# flexpcb_segmented.net
KiCad netlist of a schematic drawn in EAGLE
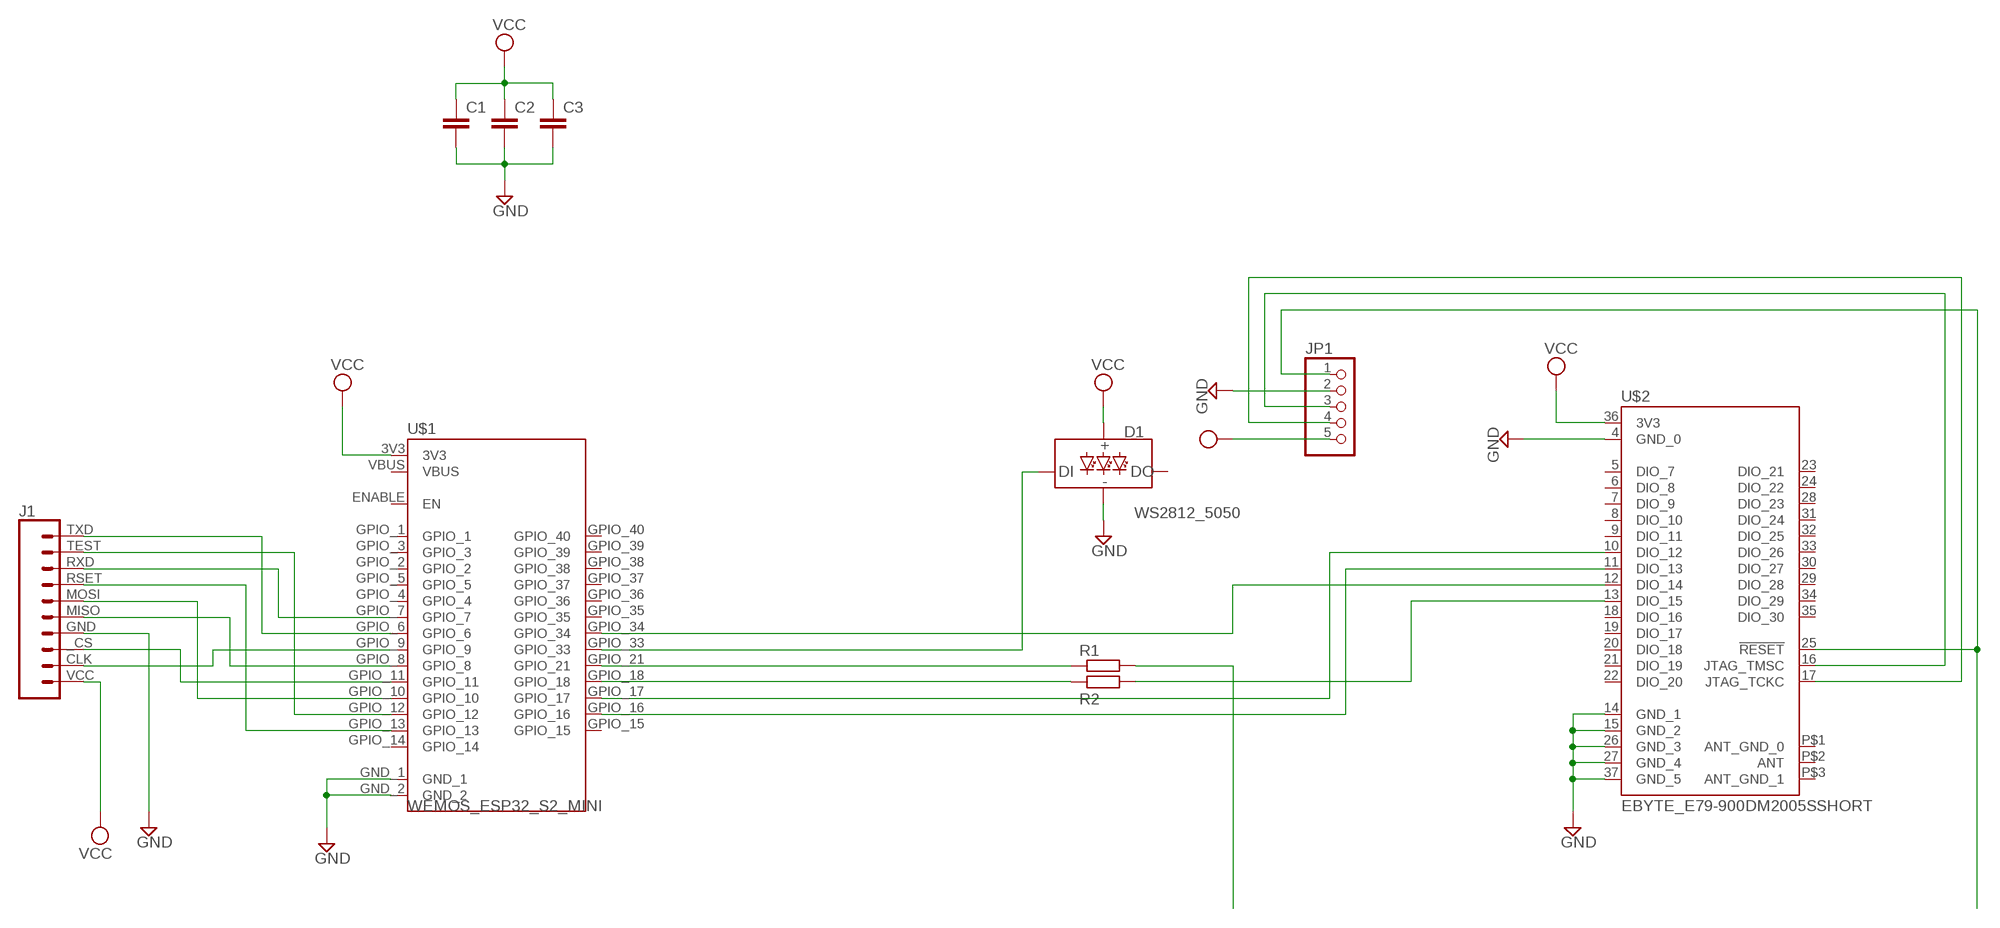
[diagram p0: schematic, sheet 1]

(export (version "E")
  (design (tool "Eeschema 10.0.6"))
  (components
    (comp (ref "C1")
      (value "C-EUC1206")
      (footprint "eagle-import:C1206")
      (libsource (lib "eagle-import") (part "C-EUC1206"))
    )
    (comp (ref "C2")
      (value "C-EUC1206")
      (footprint "eagle-import:C1206")
      (libsource (lib "eagle-import") (part "C-EUC1206"))
    )
    (comp (ref "C3")
      (value "C-EUC1206")
      (footprint "eagle-import:C1206")
      (libsource (lib "eagle-import") (part "C-EUC1206"))
    )
    (comp (ref "D1")
      (value "WS2812_5050")
      (footprint "eagle-import:WS2812-5X5-4PIN")
      (libsource (lib "eagle-import") (part "WS2812_5050"))
    )
    (comp (ref "J1")
      (value "SOLUM_ZBS_DEBUGSEGMENTED_DISPLAY")
      (footprint "eagle-import:SOLUM_ZBS_DEBUG_SEG")
      (libsource (lib "eagle-import") (part "SOLUM_ZBS_DEBUGSEGMENTED_DISPLAY"))
    )
    (comp (ref "JP1")
      (value "PINHD-1X55X2MM")
      (footprint "eagle-import:1_05X2MM")
      (libsource (lib "eagle-import") (part "PINHD-1X55X2MM"))
    )
    (comp (ref "R1")
      (value "R-EU_R0805")
      (footprint "eagle-import:R0805")
      (libsource (lib "eagle-import") (part "R-EU_R0805"))
    )
    (comp (ref "R2")
      (value "R-EU_R0805")
      (footprint "eagle-import:R0805")
      (libsource (lib "eagle-import") (part "R-EU_R0805"))
    )
    (comp (ref "U$1")
      (value "WEMOS_ESP32_S2_MINI")
      (footprint "eagle-import:WEMOS_ESP32_S2_MINI")
      (libsource (lib "eagle-import") (part "WEMOS_ESP32_S2_MINI"))
    )
    (comp (ref "U$2")
      (value "EBYTE_E79-900DM2005SSHORT")
      (footprint "eagle-import:EBYTE_E79-900DM2005S_PARTIAL")
      (libsource (lib "eagle-import") (part "EBYTE_E79-900DM2005SSHORT"))
    )
  )
  (nets
    (net (code "1") (name "/ANT") (class "Default")
      (node (ref "U$2") (pin "P$2") (pinfunction "ANT_P$2") (pintype "power_in"))
    )
    (net (code "2") (name "/ANT_GND_0") (class "Default")
      (node (ref "U$2") (pin "P$1") (pinfunction "ANT_GND_0_P$1") (pintype "power_in"))
    )
    (net (code "3") (name "/ANT_GND_1") (class "Default")
      (node (ref "U$2") (pin "P$3") (pinfunction "ANT_GND_1_P$3") (pintype "power_in"))
    )
    (net (code "4") (name "/VBUS") (class "Default")
      (node (ref "U$1") (pin "VBUS") (pinfunction "VBUS_VBUS") (pintype "power_in"))
    )
    (net (code "5") (name "GND") (class "Default")
      (node (ref "C1") (pin "2") (pinfunction "2_2") (pintype "passive"))
      (node (ref "C2") (pin "2") (pinfunction "2_2") (pintype "passive"))
      (node (ref "C3") (pin "2") (pinfunction "2_2") (pintype "passive"))
      (node (ref "D1") (pin "GND") (pinfunction "GND_GND") (pintype "bidirectional"))
      (node (ref "J1") (pin "GND") (pinfunction "4_GND") (pintype "passive"))
      (node (ref "JP1") (pin "2") (pinfunction "2_2") (pintype "passive"))
      (node (ref "U$1") (pin "GND_1") (pinfunction "GND_1_GND_1") (pintype "power_in"))
      (node (ref "U$1") (pin "GND_2") (pinfunction "GND_2_GND_2") (pintype "power_in"))
      (node (ref "U$2") (pin "14") (pinfunction "GND_1_14") (pintype "power_in"))
      (node (ref "U$2") (pin "15") (pinfunction "GND_2_15") (pintype "power_in"))
      (node (ref "U$2") (pin "26") (pinfunction "GND_3_26") (pintype "power_in"))
      (node (ref "U$2") (pin "27") (pinfunction "GND_4_27") (pintype "power_in"))
      (node (ref "U$2") (pin "37") (pinfunction "GND_5_37") (pintype "power_in"))
      (node (ref "U$2") (pin "4") (pinfunction "GND_0_4") (pintype "power_in"))
    )
    (net (code "6") (name "Net-(D1-PadDI)") (class "Default")
      (node (ref "D1") (pin "DI") (pinfunction "DI_DI") (pintype "bidirectional"))
      (node (ref "U$1") (pin "GPIO_33") (pinfunction "GPIO_33_GPIO_33") (pintype "bidirectional"))
    )
    (net (code "7") (name "Net-(J1-2)") (class "Default")
      (node (ref "J1") (pin "CLK") (pinfunction "2_CLK") (pintype "passive"))
      (node (ref "U$1") (pin "GPIO_9") (pinfunction "GPIO_9_GPIO_9") (pintype "bidirectional"))
    )
    (net (code "8") (name "Net-(J1-3)") (class "Default")
      (node (ref "J1") (pin "_CS") (pinfunction "3__CS") (pintype "passive"))
      (node (ref "U$1") (pin "GPIO_11") (pinfunction "GPIO_11_GPIO_11") (pintype "bidirectional"))
    )
    (net (code "9") (name "Net-(J1-5)") (class "Default")
      (node (ref "J1") (pin "MISO") (pinfunction "5_MISO") (pintype "passive"))
      (node (ref "U$1") (pin "GPIO_8") (pinfunction "GPIO_8_GPIO_8") (pintype "bidirectional"))
    )
    (net (code "10") (name "Net-(J1-6)") (class "Default")
      (node (ref "J1") (pin "MOSI") (pinfunction "6_MOSI") (pintype "passive"))
      (node (ref "U$1") (pin "GPIO_10") (pinfunction "GPIO_10_GPIO_10") (pintype "bidirectional"))
    )
    (net (code "11") (name "Net-(J1-7)") (class "Default")
      (node (ref "J1") (pin "RSET") (pinfunction "7_RSET") (pintype "passive"))
      (node (ref "U$1") (pin "GPIO_13") (pinfunction "GPIO_13_GPIO_13") (pintype "bidirectional"))
    )
    (net (code "12") (name "Net-(J1-8)") (class "Default")
      (node (ref "J1") (pin "RXD") (pinfunction "8_RXD") (pintype "passive"))
      (node (ref "U$1") (pin "GPIO_7") (pinfunction "GPIO_7_GPIO_7") (pintype "bidirectional"))
    )
    (net (code "13") (name "Net-(J1-9)") (class "Default")
      (node (ref "J1") (pin "TEST") (pinfunction "9_TEST") (pintype "passive"))
      (node (ref "U$1") (pin "GPIO_12") (pinfunction "GPIO_12_GPIO_12") (pintype "bidirectional"))
    )
    (net (code "14") (name "Net-(J1-10)") (class "Default")
      (node (ref "J1") (pin "TXD") (pinfunction "10_TXD") (pintype "passive"))
      (node (ref "U$1") (pin "GPIO_6") (pinfunction "GPIO_6_GPIO_6") (pintype "bidirectional"))
    )
    (net (code "15") (name "Net-(R1-Pad1)") (class "Default")
      (node (ref "R1") (pin "1") (pinfunction "1_1") (pintype "passive"))
      (node (ref "U$1") (pin "GPIO_21") (pinfunction "GPIO_21_GPIO_21") (pintype "bidirectional"))
    )
    (net (code "16") (name "Net-(R2-Pad1)") (class "Default")
      (node (ref "R2") (pin "1") (pinfunction "1_1") (pintype "passive"))
      (node (ref "U$1") (pin "GPIO_18") (pinfunction "GPIO_18_GPIO_18") (pintype "bidirectional"))
    )
    (net (code "17") (name "Net-(U$2-DIO_12)") (class "Default")
      (node (ref "U$1") (pin "GPIO_17") (pinfunction "GPIO_17_GPIO_17") (pintype "bidirectional"))
      (node (ref "U$2") (pin "10") (pinfunction "DIO_12_10") (pintype "bidirectional"))
    )
    (net (code "18") (name "Net-(U$2-DIO_13)") (class "Default")
      (node (ref "U$1") (pin "GPIO_16") (pinfunction "GPIO_16_GPIO_16") (pintype "bidirectional"))
      (node (ref "U$2") (pin "11") (pinfunction "DIO_13_11") (pintype "bidirectional"))
    )
    (net (code "19") (name "Net-(U$2-DIO_14)") (class "Default")
      (node (ref "U$1") (pin "GPIO_34") (pinfunction "GPIO_34_GPIO_34") (pintype "bidirectional"))
      (node (ref "U$2") (pin "12") (pinfunction "DIO_14_12") (pintype "bidirectional"))
    )
    (net (code "20") (name "Net-(U$2-DIO_15)") (class "Default")
      (node (ref "R2") (pin "2") (pinfunction "2_2") (pintype "passive"))
      (node (ref "U$2") (pin "13") (pinfunction "DIO_15_13") (pintype "bidirectional"))
    )
    (net (code "21") (name "Net-(U$2-JTAG_TCKC)") (class "Default")
      (node (ref "JP1") (pin "4") (pinfunction "4_4") (pintype "passive"))
      (node (ref "U$2") (pin "17") (pinfunction "JTAG_TCKC_17") (pintype "bidirectional"))
    )
    (net (code "22") (name "Net-(U$2-JTAG_TMSC)") (class "Default")
      (node (ref "JP1") (pin "3") (pinfunction "3_3") (pintype "passive"))
      (node (ref "U$2") (pin "16") (pinfunction "JTAG_TMSC_16") (pintype "bidirectional"))
    )
    (net (code "23") (name "Net-(U$2-~{RESET})") (class "Default")
      (node (ref "JP1") (pin "1") (pinfunction "1_1") (pintype "passive"))
      (node (ref "U$2") (pin "25") (pinfunction "~{RESET}_25") (pintype "bidirectional"))
    )
    (net (code "24") (name "VCC") (class "Default")
      (node (ref "C1") (pin "1") (pinfunction "1_1") (pintype "passive"))
      (node (ref "C2") (pin "1") (pinfunction "1_1") (pintype "passive"))
      (node (ref "C3") (pin "1") (pinfunction "1_1") (pintype "passive"))
      (node (ref "D1") (pin "VCC") (pinfunction "VCC_VCC") (pintype "bidirectional"))
      (node (ref "J1") (pin "VCC") (pinfunction "1_VCC") (pintype "passive"))
      (node (ref "JP1") (pin "5") (pinfunction "5_5") (pintype "passive"))
      (node (ref "U$1") (pin "3V3") (pinfunction "3V3_3V3") (pintype "power_in"))
      (node (ref "U$2") (pin "36") (pinfunction "3V3_36") (pintype "power_in"))
    )
    (net (code "25") (name "unconnected-(D1-PadDO)") (class "Default")
      (node (ref "D1") (pin "DO") (pinfunction "DO_DO") (pintype "bidirectional"))
    )
    (net (code "26") (name "unconnected-(R1-Pad2)") (class "Default")
      (node (ref "R1") (pin "2") (pinfunction "2_2") (pintype "passive"))
    )
    (net (code "27") (name "unconnected-(U$1-EN-PadENABLE)") (class "Default")
      (node (ref "U$1") (pin "ENABLE") (pinfunction "EN_ENABLE") (pintype "bidirectional"))
    )
    (net (code "28") (name "unconnected-(U$1-PadGPIO_1)") (class "Default")
      (node (ref "U$1") (pin "GPIO_1") (pinfunction "GPIO_1_GPIO_1") (pintype "bidirectional"))
    )
    (net (code "29") (name "unconnected-(U$1-PadGPIO_2)") (class "Default")
      (node (ref "U$1") (pin "GPIO_2") (pinfunction "GPIO_2_GPIO_2") (pintype "bidirectional"))
    )
    (net (code "30") (name "unconnected-(U$1-PadGPIO_3)") (class "Default")
      (node (ref "U$1") (pin "GPIO_3") (pinfunction "GPIO_3_GPIO_3") (pintype "bidirectional"))
    )
    (net (code "31") (name "unconnected-(U$1-PadGPIO_4)") (class "Default")
      (node (ref "U$1") (pin "GPIO_4") (pinfunction "GPIO_4_GPIO_4") (pintype "bidirectional"))
    )
    (net (code "32") (name "unconnected-(U$1-PadGPIO_5)") (class "Default")
      (node (ref "U$1") (pin "GPIO_5") (pinfunction "GPIO_5_GPIO_5") (pintype "bidirectional"))
    )
    (net (code "33") (name "unconnected-(U$1-PadGPIO_14)") (class "Default")
      (node (ref "U$1") (pin "GPIO_14") (pinfunction "GPIO_14_GPIO_14") (pintype "bidirectional"))
    )
    (net (code "34") (name "unconnected-(U$1-PadGPIO_15)") (class "Default")
      (node (ref "U$1") (pin "GPIO_15") (pinfunction "GPIO_15_GPIO_15") (pintype "bidirectional"))
    )
    (net (code "35") (name "unconnected-(U$1-PadGPIO_35)") (class "Default")
      (node (ref "U$1") (pin "GPIO_35") (pinfunction "GPIO_35_GPIO_35") (pintype "bidirectional"))
    )
    (net (code "36") (name "unconnected-(U$1-PadGPIO_36)") (class "Default")
      (node (ref "U$1") (pin "GPIO_36") (pinfunction "GPIO_36_GPIO_36") (pintype "bidirectional"))
    )
    (net (code "37") (name "unconnected-(U$1-PadGPIO_37)") (class "Default")
      (node (ref "U$1") (pin "GPIO_37") (pinfunction "GPIO_37_GPIO_37") (pintype "bidirectional"))
    )
    (net (code "38") (name "unconnected-(U$1-PadGPIO_38)") (class "Default")
      (node (ref "U$1") (pin "GPIO_38") (pinfunction "GPIO_38_GPIO_38") (pintype "bidirectional"))
    )
    (net (code "39") (name "unconnected-(U$1-PadGPIO_39)") (class "Default")
      (node (ref "U$1") (pin "GPIO_39") (pinfunction "GPIO_39_GPIO_39") (pintype "bidirectional"))
    )
    (net (code "40") (name "unconnected-(U$1-PadGPIO_40)") (class "Default")
      (node (ref "U$1") (pin "GPIO_40") (pinfunction "GPIO_40_GPIO_40") (pintype "bidirectional"))
    )
    (net (code "41") (name "unconnected-(U$2-DIO_7-Pad5)") (class "Default")
      (node (ref "U$2") (pin "5") (pinfunction "DIO_7_5") (pintype "bidirectional"))
    )
    (net (code "42") (name "unconnected-(U$2-DIO_8-Pad6)") (class "Default")
      (node (ref "U$2") (pin "6") (pinfunction "DIO_8_6") (pintype "bidirectional"))
    )
    (net (code "43") (name "unconnected-(U$2-DIO_9-Pad7)") (class "Default")
      (node (ref "U$2") (pin "7") (pinfunction "DIO_9_7") (pintype "bidirectional"))
    )
    (net (code "44") (name "unconnected-(U$2-DIO_10-Pad8)") (class "Default")
      (node (ref "U$2") (pin "8") (pinfunction "DIO_10_8") (pintype "bidirectional"))
    )
    (net (code "45") (name "unconnected-(U$2-DIO_11-Pad9)") (class "Default")
      (node (ref "U$2") (pin "9") (pinfunction "DIO_11_9") (pintype "bidirectional"))
    )
    (net (code "46") (name "unconnected-(U$2-DIO_16-Pad18)") (class "Default")
      (node (ref "U$2") (pin "18") (pinfunction "DIO_16_18") (pintype "bidirectional"))
    )
    (net (code "47") (name "unconnected-(U$2-DIO_17-Pad19)") (class "Default")
      (node (ref "U$2") (pin "19") (pinfunction "DIO_17_19") (pintype "bidirectional"))
    )
    (net (code "48") (name "unconnected-(U$2-DIO_18-Pad20)") (class "Default")
      (node (ref "U$2") (pin "20") (pinfunction "DIO_18_20") (pintype "bidirectional"))
    )
    (net (code "49") (name "unconnected-(U$2-DIO_19-Pad21)") (class "Default")
      (node (ref "U$2") (pin "21") (pinfunction "DIO_19_21") (pintype "bidirectional"))
    )
    (net (code "50") (name "unconnected-(U$2-DIO_20-Pad22)") (class "Default")
      (node (ref "U$2") (pin "22") (pinfunction "DIO_20_22") (pintype "bidirectional"))
    )
    (net (code "51") (name "unconnected-(U$2-DIO_21-Pad23)") (class "Default")
      (node (ref "U$2") (pin "23") (pinfunction "DIO_21_23") (pintype "bidirectional"))
    )
    (net (code "52") (name "unconnected-(U$2-DIO_22-Pad24)") (class "Default")
      (node (ref "U$2") (pin "24") (pinfunction "DIO_22_24") (pintype "bidirectional"))
    )
    (net (code "53") (name "unconnected-(U$2-DIO_23-Pad28)") (class "Default")
      (node (ref "U$2") (pin "28") (pinfunction "DIO_23_28") (pintype "bidirectional"))
    )
    (net (code "54") (name "unconnected-(U$2-DIO_24-Pad31)") (class "Default")
      (node (ref "U$2") (pin "31") (pinfunction "DIO_24_31") (pintype "bidirectional"))
    )
    (net (code "55") (name "unconnected-(U$2-DIO_25-Pad32)") (class "Default")
      (node (ref "U$2") (pin "32") (pinfunction "DIO_25_32") (pintype "bidirectional"))
    )
    (net (code "56") (name "unconnected-(U$2-DIO_26-Pad33)") (class "Default")
      (node (ref "U$2") (pin "33") (pinfunction "DIO_26_33") (pintype "bidirectional"))
    )
    (net (code "57") (name "unconnected-(U$2-DIO_27-Pad30)") (class "Default")
      (node (ref "U$2") (pin "30") (pinfunction "DIO_27_30") (pintype "bidirectional"))
    )
    (net (code "58") (name "unconnected-(U$2-DIO_28-Pad29)") (class "Default")
      (node (ref "U$2") (pin "29") (pinfunction "DIO_28_29") (pintype "bidirectional"))
    )
    (net (code "59") (name "unconnected-(U$2-DIO_29-Pad34)") (class "Default")
      (node (ref "U$2") (pin "34") (pinfunction "DIO_29_34") (pintype "bidirectional"))
    )
    (net (code "60") (name "unconnected-(U$2-DIO_30-Pad35)") (class "Default")
      (node (ref "U$2") (pin "35") (pinfunction "DIO_30_35") (pintype "bidirectional"))
    )
  )
)
